# openSX70_LENS_BELLOWS_V5_0-SEEED_2018022.net
KiCad netlist of a schematic drawn in EAGLE
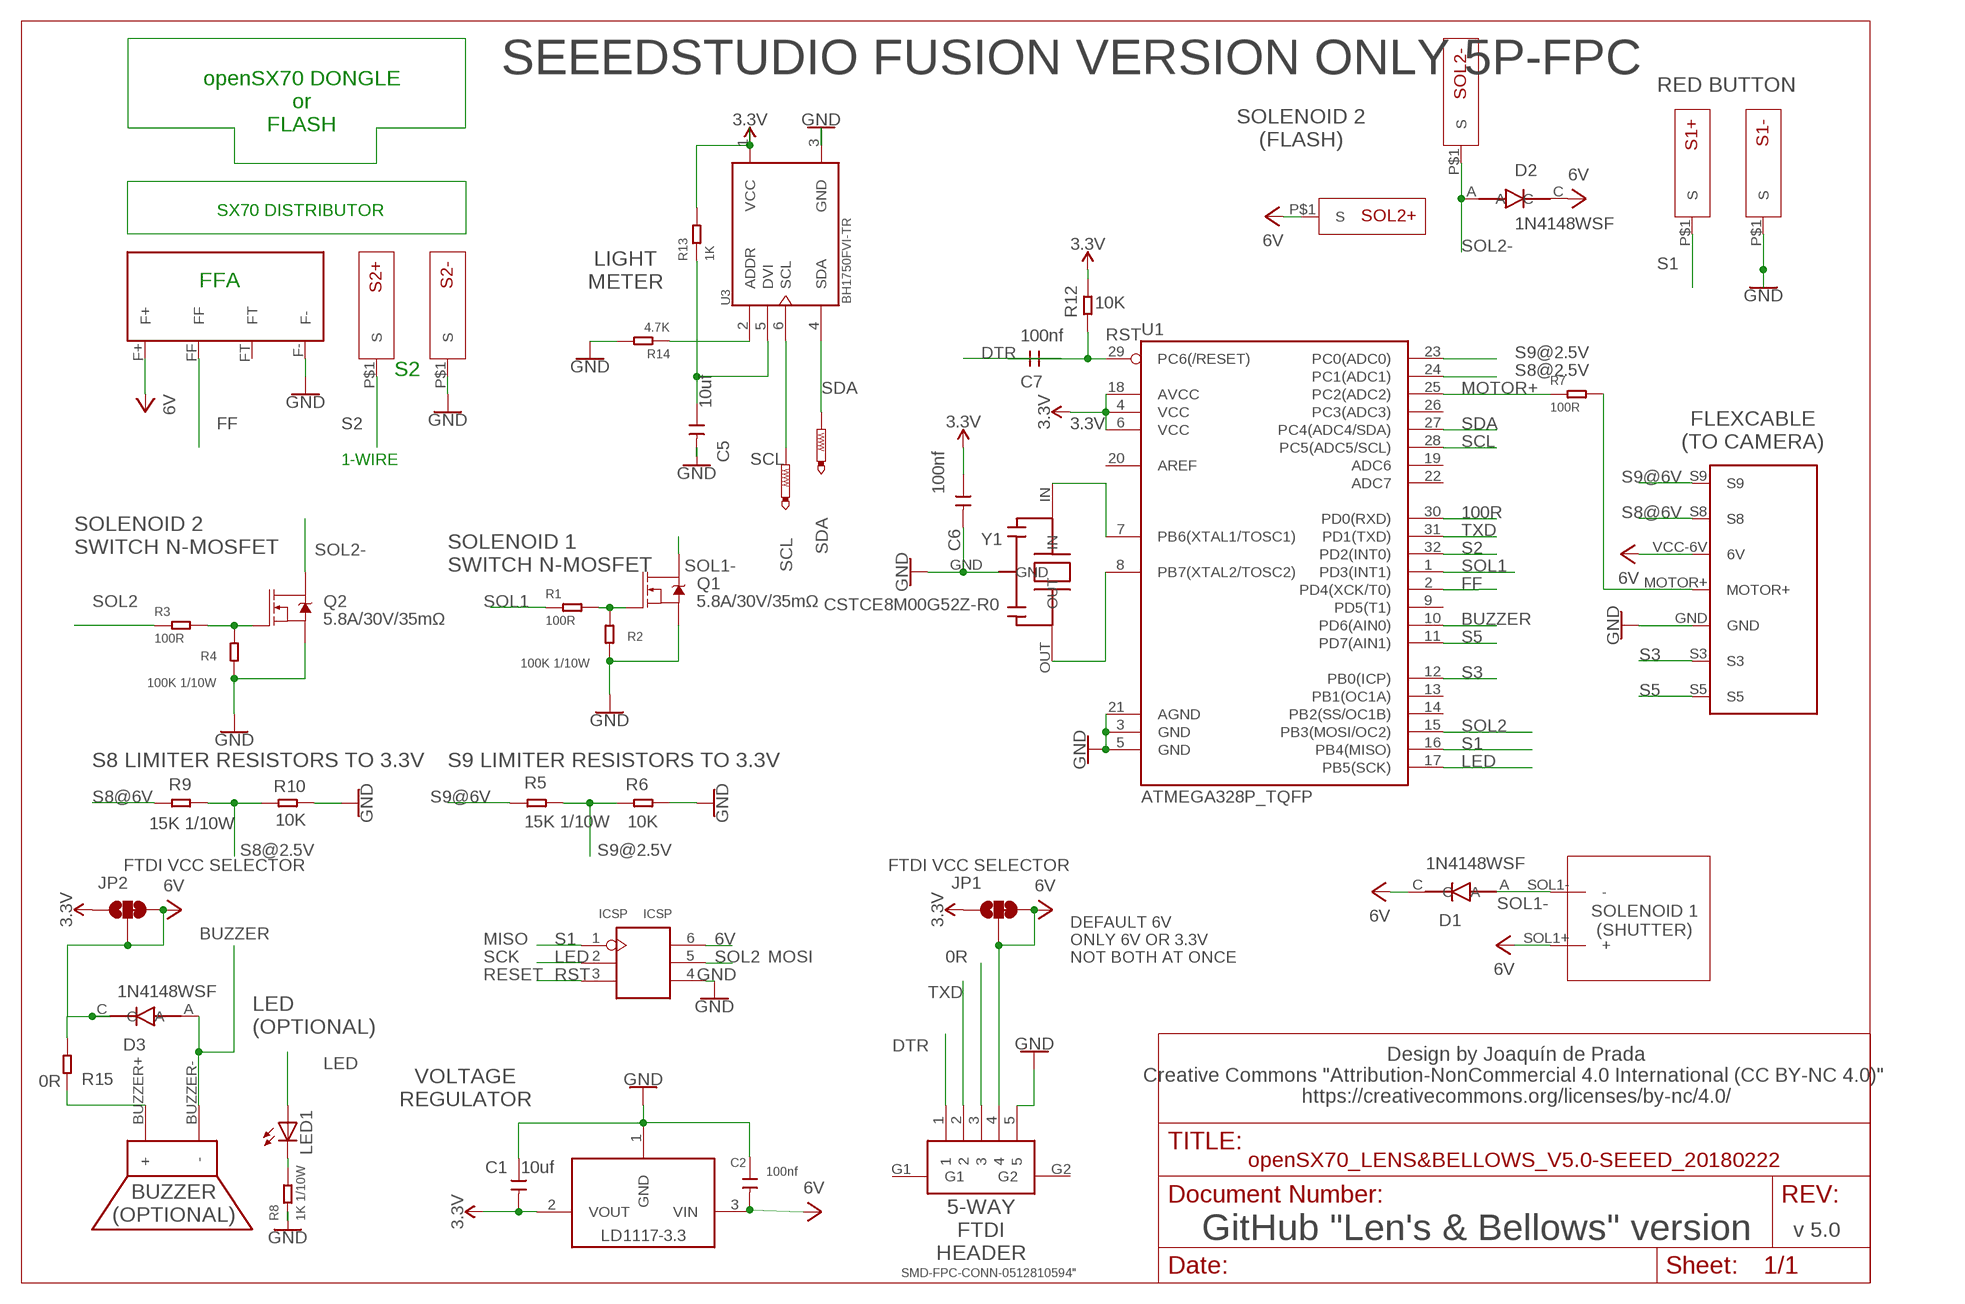
[diagram p0: schematic, sheet 1]

(export (version "E")
  (design (tool "Eeschema 10.0.6"))
  (components
    (comp (ref "C1")
      (value "10uf")
      (footprint "eagle-import:C0603")
      (fields (field (name "MPN") "CC0603KRX5R6BB106"))
      (libsource (lib "eagle-import") (part "CERAMIC-10UF-10V-10%-X5R(0603)"))
    )
    (comp (ref "C2")
      (value "100nf")
      (footprint "eagle-import:C0603")
      (fields (field (name "MPN") "CC0603KRX7R9BB104"))
      (libsource (lib "eagle-import") (part "CERAMIC-100NF-50V-10%-X7R(0603)"))
    )
    (comp (ref "C5")
      (value "10uf")
      (footprint "eagle-import:C0603")
      (fields (field (name "MPN") "CC0603KRX5R6BB106"))
      (libsource (lib "eagle-import") (part "CERAMIC-10UF-10V-10%-X5R(0603)"))
    )
    (comp (ref "C6")
      (value "100nf")
      (footprint "eagle-import:C0603")
      (fields (field (name "MPN") "CC0603KRX7R9BB104"))
      (libsource (lib "eagle-import") (part "CERAMIC-100NF-50V-10%-X7R(0603)"))
    )
    (comp (ref "C7")
      (value "100nf")
      (footprint "eagle-import:C0603")
      (fields (field (name "MPN") "CC0603KRX7R9BB104"))
      (libsource (lib "eagle-import") (part "CERAMIC-100NF-50V-10%-X7R(0603)"))
    )
    (comp (ref "D1")
      (value "1N4148WSF")
      (footprint "eagle-import:SODFL2512X100N")
      (fields (field (name "MANUFACTURER") "Fairchild Semiconductor"))
      (libsource (lib "eagle-import") (part "1N4148WS"))
    )
    (comp (ref "D2")
      (value "1N4148WSF")
      (footprint "eagle-import:SODFL2512X100N")
      (fields (field (name "MANUFACTURER") "Fairchild Semiconductor"))
      (libsource (lib "eagle-import") (part "1N4148WS"))
    )
    (comp (ref "D3")
      (value "1N4148WSF")
      (footprint "eagle-import:SODFL2512X100N")
      (fields (field (name "MANUFACTURER") "Fairchild Semiconductor"))
      (libsource (lib "eagle-import") (part "1N4148WS"))
    )
    (comp (ref "ICSP")
      (value "ICSP")
      (footprint "eagle-import:H2X3-2.54")
      (libsource (lib "eagle-import") (part "ICSP"))
    )
    (comp (ref "JP1")
      (value "FTDI VCC SELECTOR")
      (footprint "eagle-import:SMT-JUMPER_3_1-NC_TRACE_SILK")
      (libsource (lib "eagle-import") (part "JUMPER-SMT_3_1-NC_TRACE_SILK"))
    )
    (comp (ref "JP2")
      (value "FTDI VCC SELECTOR")
      (footprint "eagle-import:SMT-JUMPER_3_1-NC_TRACE_SILK")
      (libsource (lib "eagle-import") (part "JUMPER-SMT_3_1-NC_TRACE_SILK"))
    )
    (comp (ref "LD11172.5V")
      (value "LD1117 2.5V")
      (footprint "eagle-import:SOT223")
      (fields (field (name "MF") "Advanced Monolithic Systems") (field (name "MP") "AMS1117-5.0"))
      (libsource (lib "eagle-import") (part "LD1117-3.3"))
    )
    (comp (ref "LED1")
      (value "LEDCHIPLED_0805")
      (footprint "eagle-import:CHIPLED_0805")
      (libsource (lib "eagle-import") (part "LEDCHIPLED_0805"))
    )
    (comp (ref "Q1")
      (value "5.8A/30V/35mΩ")
      (footprint "eagle-import:SOT23-3")
      (libsource (lib "eagle-import") (part "MOSFET-NCH-AO3404A"))
    )
    (comp (ref "Q2")
      (value "5.8A/30V/35mΩ")
      (footprint "eagle-import:SOT23-3")
      (libsource (lib "eagle-import") (part "MOSFET-NCH-AO3404A"))
    )
    (comp (ref "R1")
      (value "100R")
      (footprint "eagle-import:R0603")
      (fields (field (name "MPN") "RC0603JR-07100RL"))
      (libsource (lib "eagle-import") (part "SMD-RES-100R-5%-1/10W(0603)"))
    )
    (comp (ref "R2")
      (value "100K 1/10W")
      (footprint "eagle-import:R0603")
      (fields (field (name "MPN") "RC0603JR-07100KL"))
      (libsource (lib "eagle-import") (part "SMD-RES-100K-5%-1/10W(0603)"))
    )
    (comp (ref "R3")
      (value "100R")
      (footprint "eagle-import:R0603")
      (fields (field (name "MPN") "RC0603JR-07100RL"))
      (libsource (lib "eagle-import") (part "SMD-RES-100R-5%-1/10W(0603)"))
    )
    (comp (ref "R4")
      (value "100K 1/10W")
      (footprint "eagle-import:R0603")
      (fields (field (name "MPN") "RC0603JR-07100KL"))
      (libsource (lib "eagle-import") (part "SMD-RES-100K-5%-1/10W(0603)"))
    )
    (comp (ref "R5")
      (value "15K 1/10W")
      (footprint "eagle-import:R0603")
      (fields (field (name "MPN") "RC0603FR-0715KL"))
      (libsource (lib "eagle-import") (part "SMD-RES-15K-1%-1/10W(0603)"))
    )
    (comp (ref "R6")
      (value "10K")
      (footprint "eagle-import:R0603")
      (fields (field (name "MPN") "RC0603FR-0710KL"))
      (libsource (lib "eagle-import") (part "SMD-RES-10K-1%-1/10W(0603)"))
    )
    (comp (ref "R7")
      (value "100R")
      (footprint "eagle-import:R0603")
      (fields (field (name "MPN") "RC0603JR-07100RL"))
      (libsource (lib "eagle-import") (part "SMD-RES-100R-5%-1/10W(0603)"))
    )
    (comp (ref "R8")
      (value "1K 1/10W")
      (footprint "eagle-import:R0603")
      (fields (field (name "MPN") "RC0603JR-071KL"))
      (libsource (lib "eagle-import") (part "SMD-RES-1K-5%-1/10W(0603)"))
    )
    (comp (ref "R9")
      (value "15K 1/10W")
      (footprint "eagle-import:R0603")
      (fields (field (name "MPN") "RC0603FR-0715KL"))
      (libsource (lib "eagle-import") (part "SMD-RES-15K-1%-1/10W(0603)"))
    )
    (comp (ref "R10")
      (value "10K")
      (footprint "eagle-import:R0603")
      (fields (field (name "MPN") "RC0603FR-0710KL"))
      (libsource (lib "eagle-import") (part "SMD-RES-10K-1%-1/10W(0603)"))
    )
    (comp (ref "R12")
      (value "10K")
      (footprint "eagle-import:R0603")
      (fields (field (name "MPN") "RC0603FR-0710KL"))
      (libsource (lib "eagle-import") (part "SMD-RES-10K-1%-1/10W(0603)"))
    )
    (comp (ref "R13")
      (value "1K")
      (footprint "eagle-import:R0603")
      (fields (field (name "MPN") "RC0603FR-071KL"))
      (libsource (lib "eagle-import") (part "SMD-RES-1K-1%-1/10W(0603)"))
    )
    (comp (ref "R14")
      (value "4.7K")
      (footprint "eagle-import:R0603")
      (fields (field (name "MPN") "RC0603JR-074K7L"))
      (libsource (lib "eagle-import") (part "SMD-RES-4.7K-5%-1/10W(0603)"))
    )
    (comp (ref "R15")
      (value "0R")
      (footprint "eagle-import:R0603")
      (fields (field (name "MPN") "RC0603JR-07100RL"))
      (libsource (lib "eagle-import") (part "SMD-RES-100R-5%-1/10W(0603)"))
    )
    (comp (ref "S1+")
      (value "SX70-S-PAD-NEW")
      (footprint "eagle-import:SX70-S-PAD2")
      (libsource (lib "eagle-import") (part "SX70-S-PAD-NEW"))
    )
    (comp (ref "S1-")
      (value "SX70-S-PAD-NEW")
      (footprint "eagle-import:SX70-S-PAD2")
      (libsource (lib "eagle-import") (part "SX70-S-PAD-NEW"))
    )
    (comp (ref "S2+")
      (value "SX70-S-PAD-NEW")
      (footprint "eagle-import:SX70-S-PAD2")
      (libsource (lib "eagle-import") (part "SX70-S-PAD-NEW"))
    )
    (comp (ref "S2-")
      (value "SX70-S-PAD-NEW")
      (footprint "eagle-import:SX70-S-PAD2")
      (libsource (lib "eagle-import") (part "SX70-S-PAD-NEW"))
    )
    (comp (ref "SCL")
      (value "PTR1TP08R")
      (footprint "eagle-import:TP08R")
      (libsource (lib "eagle-import") (part "PTR1TP08R"))
    )
    (comp (ref "SDA")
      (value "PTR1TP08R")
      (footprint "eagle-import:TP08R")
      (libsource (lib "eagle-import") (part "PTR1TP08R"))
    )
    (comp (ref "SOL1")
      (value "SX70-SOLENOID1-2PADS")
      (footprint "eagle-import:SX70-SOLENOID1-2")
      (libsource (lib "eagle-import") (part "SX70-SOLENOID1-2PADS"))
    )
    (comp (ref "SOL2+")
      (value "SX70-S-PAD-NEW")
      (footprint "eagle-import:SX70-S-PAD2")
      (libsource (lib "eagle-import") (part "SX70-S-PAD-NEW"))
    )
    (comp (ref "SOL2-")
      (value "SX70-S-PAD-NEW")
      (footprint "eagle-import:SX70-S-PAD2")
      (libsource (lib "eagle-import") (part "SX70-S-PAD-NEW"))
    )
    (comp (ref "U$1")
      (value "SX70-7-PAD")
      (footprint "eagle-import:SX70-7-PAD")
      (libsource (lib "eagle-import") (part "SX70-7-PAD"))
    )
    (comp (ref "U$2")
      (value "FFA")
      (footprint "eagle-import:FFA-PAD-PACKAGE")
      (libsource (lib "eagle-import") (part "SX70-FFA-PAD"))
    )
    (comp (ref "U$3")
      (value "CSET8-5G_V2")
      (footprint "eagle-import:CSET8-5G_PACKAGE")
      (libsource (lib "eagle-import") (part "CSET8-5G_V2"))
    )
    (comp (ref "U$4")
      (value "SMD-FPC-CONN-0512810594\"")
      (footprint "eagle-import:51281-0594")
      (libsource (lib "eagle-import") (part "SMD-FPC-CONN-0512810594{dblquote}"))
    )
    (comp (ref "U1")
      (value "ATMEGA328P_TQFP")
      (footprint "eagle-import:TQFP32-08")
      (libsource (lib "eagle-import") (part "ATMEGA328P_TQFP"))
    )
    (comp (ref "U3")
      (value "BH1750FVI-TR")
      (footprint "eagle-import:SOTFL50P300X75-6N")
      (fields (field (name "MF") "Rohm"))
      (libsource (lib "eagle-import") (part "BH1750FVI-TR"))
    )
    (comp (ref "Y1")
      (value "CSTCE8M00G52Z-R0")
      (footprint "eagle-import:CFP95P160X100-3N")
      (fields (field (name "MF") "Murata") (field (name "MP") "CSTCE16M0V53-R0"))
      (libsource (lib "eagle-import") (part "CSTCE16M0V53-R0"))
    )
  )
  (nets
    (net (code "1") (name "/0R") (class "Default")
      (node (ref "U$4") (pin "3") (pinfunction "3_3") (pintype "bidirectional"))
    )
    (net (code "2") (name "/100R") (class "Default")
      (node (ref "U1") (pin "30") (pinfunction "PD0(RXD)_30") (pintype "bidirectional"))
    )
    (net (code "3") (name "/BUZZER") (class "Default")
      (node (ref "D3") (pin "A") (pinfunction "A_A") (pintype "passive"))
      (node (ref "U$3") (pin "BUZZER-") (pinfunction "-_BUZZER-") (pintype "bidirectional"))
      (node (ref "U1") (pin "10") (pinfunction "PD6(AIN0)_10") (pintype "bidirectional"))
    )
    (net (code "4") (name "/DTR") (class "Default")
      (node (ref "C7") (pin "1") (pinfunction "1_1") (pintype "passive"))
      (node (ref "U$4") (pin "1") (pinfunction "1_1") (pintype "bidirectional"))
    )
    (net (code "5") (name "/FF") (class "Default")
      (node (ref "U$2") (pin "FF") (pinfunction "FF_FF") (pintype "bidirectional"))
      (node (ref "U1") (pin "2") (pinfunction "PD4(XCK/T0)_2") (pintype "bidirectional"))
    )
    (net (code "6") (name "/LED") (class "Default")
      (node (ref "ICSP") (pin "2") (pinfunction "SCK_2") (pintype "bidirectional"))
      (node (ref "LED1") (pin "A") (pinfunction "A_A") (pintype "passive"))
      (node (ref "U1") (pin "17") (pinfunction "PB5(SCK)_17") (pintype "bidirectional"))
    )
    (net (code "7") (name "/MOTOR+") (class "Default")
      (node (ref "R7") (pin "1") (pinfunction "1_1") (pintype "passive"))
      (node (ref "U1") (pin "25") (pinfunction "PC2(ADC2)_25") (pintype "bidirectional"))
    )
    (net (code "8") (name "/RST") (class "Default")
      (node (ref "C7") (pin "2") (pinfunction "2_2") (pintype "passive"))
      (node (ref "ICSP") (pin "3") (pinfunction "RST_3") (pintype "bidirectional"))
      (node (ref "R12") (pin "1") (pinfunction "1_1") (pintype "passive"))
      (node (ref "U1") (pin "29") (pinfunction "PC6(/RESET)_29") (pintype "bidirectional"))
    )
    (net (code "9") (name "/S1") (class "Default")
      (node (ref "ICSP") (pin "1") (pinfunction "MISO_1") (pintype "bidirectional"))
      (node (ref "S1+") (pin "P$1") (pinfunction "S_P$1") (pintype "bidirectional"))
      (node (ref "U1") (pin "16") (pinfunction "PB4(MISO)_16") (pintype "bidirectional"))
    )
    (net (code "10") (name "/S2") (class "Default")
      (node (ref "S2+") (pin "P$1") (pinfunction "S_P$1") (pintype "bidirectional"))
      (node (ref "U1") (pin "32") (pinfunction "PD2(INT0)_32") (pintype "bidirectional"))
    )
    (net (code "11") (name "/S3") (class "Default")
      (node (ref "U$1") (pin "S3") (pinfunction "S3_S3") (pintype "bidirectional"))
      (node (ref "U1") (pin "12") (pinfunction "PB0(ICP)_12") (pintype "bidirectional"))
    )
    (net (code "12") (name "/S5") (class "Default")
      (node (ref "U$1") (pin "S5") (pinfunction "S5_S5") (pintype "bidirectional"))
      (node (ref "U1") (pin "11") (pinfunction "PD7(AIN1)_11") (pintype "bidirectional"))
    )
    (net (code "13") (name "/S8@2.5V") (class "Default")
      (node (ref "R10") (pin "1") (pinfunction "1_1") (pintype "passive"))
      (node (ref "R9") (pin "2") (pinfunction "2_2") (pintype "passive"))
      (node (ref "U1") (pin "24") (pinfunction "PC1(ADC1)_24") (pintype "bidirectional"))
    )
    (net (code "14") (name "/S8@6V") (class "Default")
      (node (ref "R9") (pin "1") (pinfunction "1_1") (pintype "passive"))
      (node (ref "U$1") (pin "S8") (pinfunction "S8_S8") (pintype "bidirectional"))
    )
    (net (code "15") (name "/S9@2.5V") (class "Default")
      (node (ref "R5") (pin "2") (pinfunction "2_2") (pintype "passive"))
      (node (ref "R6") (pin "1") (pinfunction "1_1") (pintype "passive"))
      (node (ref "U1") (pin "23") (pinfunction "PC0(ADC0)_23") (pintype "bidirectional"))
    )
    (net (code "16") (name "/S9@6V") (class "Default")
      (node (ref "R5") (pin "1") (pinfunction "1_1") (pintype "passive"))
      (node (ref "U$1") (pin "S9") (pinfunction "S9_S9") (pintype "bidirectional"))
    )
    (net (code "17") (name "/SCL") (class "Default")
      (node (ref "SCL") (pin "TP") (pinfunction "TP_TP") (pintype "input"))
      (node (ref "U1") (pin "28") (pinfunction "PC5(ADC5/SCL)_28") (pintype "bidirectional"))
      (node (ref "U3") (pin "6") (pinfunction "SCL_6") (pintype "input"))
    )
    (net (code "18") (name "/SDA") (class "Default")
      (node (ref "SDA") (pin "TP") (pinfunction "TP_TP") (pintype "input"))
      (node (ref "U1") (pin "27") (pinfunction "PC4(ADC4/SDA)_27") (pintype "bidirectional"))
      (node (ref "U3") (pin "4") (pinfunction "SDA_4") (pintype "bidirectional"))
    )
    (net (code "19") (name "/SOL1") (class "Default")
      (node (ref "R1") (pin "1") (pinfunction "1_1") (pintype "passive"))
      (node (ref "U1") (pin "1") (pinfunction "PD3(INT1)_1") (pintype "bidirectional"))
    )
    (net (code "20") (name "/SOL1-") (class "Default")
      (node (ref "D1") (pin "A") (pinfunction "A_A") (pintype "passive"))
      (node (ref "Q1") (pin "3") (pinfunction "D_3") (pintype "bidirectional"))
      (node (ref "SOL1") (pin "SOL1-") (pinfunction "-_SOL1-") (pintype "bidirectional"))
    )
    (net (code "21") (name "/SOL2") (class "Default")
      (node (ref "ICSP") (pin "5") (pinfunction "MOSI_5") (pintype "bidirectional"))
      (node (ref "R3") (pin "1") (pinfunction "1_1") (pintype "passive"))
      (node (ref "U1") (pin "15") (pinfunction "PB3(MOSI/OC2)_15") (pintype "bidirectional"))
    )
    (net (code "22") (name "/SOL2-") (class "Default")
      (node (ref "D2") (pin "A") (pinfunction "A_A") (pintype "passive"))
      (node (ref "Q2") (pin "3") (pinfunction "D_3") (pintype "bidirectional"))
      (node (ref "SOL2-") (pin "P$1") (pinfunction "S_P$1") (pintype "bidirectional"))
    )
    (net (code "23") (name "/TXD") (class "Default")
      (node (ref "U$4") (pin "2") (pinfunction "2_2") (pintype "bidirectional"))
      (node (ref "U1") (pin "31") (pinfunction "PD1(TXD)_31") (pintype "bidirectional"))
    )
    (net (code "24") (name "3.3V") (class "Default")
      (node (ref "C1") (pin "2") (pinfunction "2_2") (pintype "passive"))
      (node (ref "C6") (pin "1") (pinfunction "1_1") (pintype "passive"))
      (node (ref "JP1") (pin "1") (pinfunction "1_1") (pintype "passive"))
      (node (ref "JP2") (pin "1") (pinfunction "1_1") (pintype "passive"))
      (node (ref "LD11172.5V") (pin "2") (pinfunction "VOUT_2") (pintype "bidirectional"))
      (node (ref "R12") (pin "2") (pinfunction "2_2") (pintype "passive"))
      (node (ref "R13") (pin "2") (pinfunction "2_2") (pintype "passive"))
      (node (ref "U1") (pin "18") (pinfunction "AVCC_18") (pintype "bidirectional"))
      (node (ref "U1") (pin "4") (pinfunction "VCC_4") (pintype "bidirectional"))
      (node (ref "U1") (pin "6") (pinfunction "VCC_6") (pintype "bidirectional"))
      (node (ref "U3") (pin "1") (pinfunction "VCC_1") (pintype "power_in"))
    )
    (net (code "25") (name "6V") (class "Default")
      (node (ref "C2") (pin "2") (pinfunction "2_2") (pintype "passive"))
      (node (ref "D1") (pin "C") (pinfunction "C_C") (pintype "passive"))
      (node (ref "D2") (pin "C") (pinfunction "C_C") (pintype "passive"))
      (node (ref "D3") (pin "C") (pinfunction "C_C") (pintype "passive"))
      (node (ref "ICSP") (pin "6") (pinfunction "VCC_6") (pintype "bidirectional"))
      (node (ref "JP1") (pin "2") (pinfunction "2_2") (pintype "passive"))
      (node (ref "JP1") (pin "3") (pinfunction "3_3") (pintype "passive"))
      (node (ref "JP2") (pin "2") (pinfunction "2_2") (pintype "passive"))
      (node (ref "JP2") (pin "3") (pinfunction "3_3") (pintype "passive"))
      (node (ref "LD11172.5V") (pin "3") (pinfunction "VIN_3") (pintype "bidirectional"))
      (node (ref "R15") (pin "2") (pinfunction "2_2") (pintype "passive"))
      (node (ref "SOL1") (pin "SOL1+") (pinfunction "+_SOL1+") (pintype "bidirectional"))
      (node (ref "SOL2+") (pin "P$1") (pinfunction "S_P$1") (pintype "bidirectional"))
      (node (ref "U$1") (pin "VCC-6V") (pinfunction "6V_VCC-6V") (pintype "bidirectional"))
      (node (ref "U$2") (pin "F+") (pinfunction "F+_F+") (pintype "bidirectional"))
      (node (ref "U$4") (pin "4") (pinfunction "4_4") (pintype "bidirectional"))
    )
    (net (code "26") (name "GND") (class "Default")
      (node (ref "C1") (pin "1") (pinfunction "1_1") (pintype "passive"))
      (node (ref "C2") (pin "1") (pinfunction "1_1") (pintype "passive"))
      (node (ref "C5") (pin "2") (pinfunction "2_2") (pintype "passive"))
      (node (ref "C6") (pin "2") (pinfunction "2_2") (pintype "passive"))
      (node (ref "ICSP") (pin "4") (pinfunction "GND_4") (pintype "bidirectional"))
      (node (ref "LD11172.5V") (pin "1") (pinfunction "GND_1") (pintype "bidirectional"))
      (node (ref "Q1") (pin "2") (pinfunction "S_2") (pintype "bidirectional"))
      (node (ref "Q2") (pin "2") (pinfunction "S_2") (pintype "bidirectional"))
      (node (ref "R10") (pin "2") (pinfunction "2_2") (pintype "passive"))
      (node (ref "R14") (pin "2") (pinfunction "2_2") (pintype "passive"))
      (node (ref "R2") (pin "1") (pinfunction "1_1") (pintype "passive"))
      (node (ref "R4") (pin "1") (pinfunction "1_1") (pintype "passive"))
      (node (ref "R6") (pin "2") (pinfunction "2_2") (pintype "passive"))
      (node (ref "R8") (pin "1") (pinfunction "1_1") (pintype "passive"))
      (node (ref "S1-") (pin "P$1") (pinfunction "S_P$1") (pintype "bidirectional"))
      (node (ref "S2-") (pin "P$1") (pinfunction "S_P$1") (pintype "bidirectional"))
      (node (ref "U$1") (pin "GND") (pinfunction "GND_GND") (pintype "bidirectional"))
      (node (ref "U$2") (pin "F-") (pinfunction "F-_F-") (pintype "bidirectional"))
      (node (ref "U$4") (pin "5") (pinfunction "5_5") (pintype "bidirectional"))
      (node (ref "U1") (pin "21") (pinfunction "AGND_21") (pintype "bidirectional"))
      (node (ref "U1") (pin "3") (pinfunction "GND_3") (pintype "bidirectional"))
      (node (ref "U1") (pin "5") (pinfunction "GND_5") (pintype "bidirectional"))
      (node (ref "U3") (pin "3") (pinfunction "GND_3") (pintype "power_in"))
      (node (ref "Y1") (pin "GND") (pinfunction "GND_GND") (pintype "passive"))
    )
    (net (code "27") (name "Net-(LED1-PadC)") (class "Default")
      (node (ref "LED1") (pin "C") (pinfunction "C_C") (pintype "passive"))
      (node (ref "R8") (pin "2") (pinfunction "2_2") (pintype "passive"))
    )
    (net (code "28") (name "Net-(Q1-G)") (class "Default")
      (node (ref "Q1") (pin "1") (pinfunction "G_1") (pintype "bidirectional"))
      (node (ref "R1") (pin "2") (pinfunction "2_2") (pintype "passive"))
      (node (ref "R2") (pin "2") (pinfunction "2_2") (pintype "passive"))
    )
    (net (code "29") (name "Net-(Q2-G)") (class "Default")
      (node (ref "Q2") (pin "1") (pinfunction "G_1") (pintype "bidirectional"))
      (node (ref "R3") (pin "2") (pinfunction "2_2") (pintype "passive"))
      (node (ref "R4") (pin "2") (pinfunction "2_2") (pintype "passive"))
    )
    (net (code "30") (name "Net-(R7-Pad2)") (class "Default")
      (node (ref "R7") (pin "2") (pinfunction "2_2") (pintype "passive"))
      (node (ref "U$1") (pin "MOTOR+") (pinfunction "MOTOR+_MOTOR+") (pintype "bidirectional"))
    )
    (net (code "31") (name "Net-(U$3-+)") (class "Default")
      (node (ref "R15") (pin "1") (pinfunction "1_1") (pintype "passive"))
      (node (ref "U$3") (pin "BUZZER+") (pinfunction "+_BUZZER+") (pintype "bidirectional"))
    )
    (net (code "32") (name "Net-(U1-PB6(XTAL1{slash}TOSC1))") (class "Default")
      (node (ref "U1") (pin "7") (pinfunction "PB6(XTAL1/TOSC1)_7") (pintype "bidirectional"))
      (node (ref "Y1") (pin "IN") (pinfunction "IN_IN") (pintype "input"))
    )
    (net (code "33") (name "Net-(U1-PB7(XTAL2{slash}TOSC2))") (class "Default")
      (node (ref "U1") (pin "8") (pinfunction "PB7(XTAL2/TOSC2)_8") (pintype "bidirectional"))
      (node (ref "Y1") (pin "OUT") (pinfunction "OUT_OUT") (pintype "output"))
    )
    (net (code "34") (name "Net-(U3-ADDR)") (class "Default")
      (node (ref "R14") (pin "1") (pinfunction "1_1") (pintype "passive"))
      (node (ref "U3") (pin "2") (pinfunction "ADDR_2") (pintype "input"))
    )
    (net (code "35") (name "Net-(U3-DVI)") (class "Default")
      (node (ref "C5") (pin "1") (pinfunction "1_1") (pintype "passive"))
      (node (ref "R13") (pin "1") (pinfunction "1_1") (pintype "passive"))
      (node (ref "U3") (pin "5") (pinfunction "DVI_5") (pintype "input"))
    )
    (net (code "36") (name "unconnected-(U$2-PadFT)") (class "Default")
      (node (ref "U$2") (pin "FT") (pinfunction "FT_FT") (pintype "bidirectional"))
    )
    (net (code "37") (name "unconnected-(U$4-PadG1)") (class "Default")
      (node (ref "U$4") (pin "G1") (pinfunction "G1_G1") (pintype "bidirectional"))
    )
    (net (code "38") (name "unconnected-(U$4-PadG2)") (class "Default")
      (node (ref "U$4") (pin "G2") (pinfunction "G2_G2") (pintype "bidirectional"))
    )
    (net (code "39") (name "unconnected-(U1-ADC6-Pad19)") (class "Default")
      (node (ref "U1") (pin "19") (pinfunction "ADC6_19") (pintype "bidirectional"))
    )
    (net (code "40") (name "unconnected-(U1-ADC7-Pad22)") (class "Default")
      (node (ref "U1") (pin "22") (pinfunction "ADC7_22") (pintype "bidirectional"))
    )
    (net (code "41") (name "unconnected-(U1-AREF-Pad20)") (class "Default")
      (node (ref "U1") (pin "20") (pinfunction "AREF_20") (pintype "bidirectional"))
    )
    (net (code "42") (name "unconnected-(U1-PB1(OC1A)-Pad13)") (class "Default")
      (node (ref "U1") (pin "13") (pinfunction "PB1(OC1A)_13") (pintype "bidirectional"))
    )
    (net (code "43") (name "unconnected-(U1-PB2(SS{slash}OC1B)-Pad14)") (class "Default")
      (node (ref "U1") (pin "14") (pinfunction "PB2(SS/OC1B)_14") (pintype "bidirectional"))
    )
    (net (code "44") (name "unconnected-(U1-PC3(ADC3)-Pad26)") (class "Default")
      (node (ref "U1") (pin "26") (pinfunction "PC3(ADC3)_26") (pintype "bidirectional"))
    )
    (net (code "45") (name "unconnected-(U1-PD5(T1)-Pad9)") (class "Default")
      (node (ref "U1") (pin "9") (pinfunction "PD5(T1)_9") (pintype "bidirectional"))
    )
  )
)
